# power.net
KiCad netlist of a schematic drawn in Altium Designer
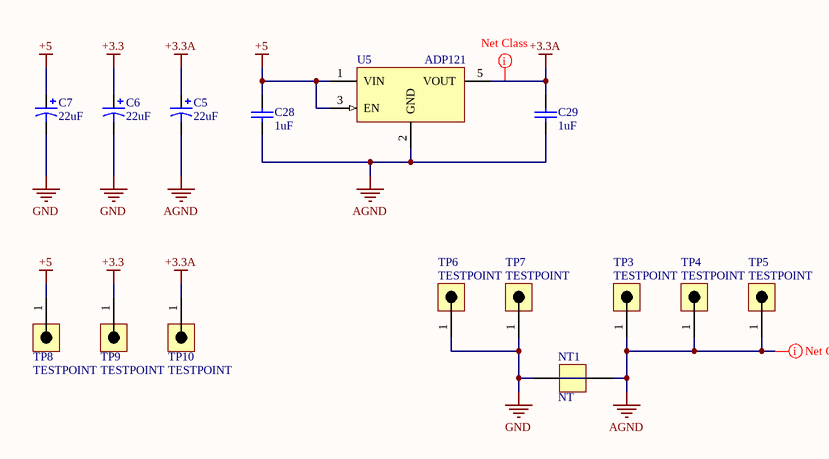
[diagram p0: power.SchDoc]

(export (version "E")
  (design (tool "Eeschema 10.0.6"))
  (components
    (comp (ref "C5")
      (value "22uF")
      (footprint "C0805")
      (description "Polarized Capacitor (Radial)")
      (fields (field (name "Comment") "Cap Pol1") (field (name "PUBLISHER") "Altium Limited"))
      (libsource (lib "Miscellaneous Devices") (part "Cap Pol1"))
    )
    (comp (ref "C6")
      (value "22uF")
      (footprint "C0805")
      (description "Polarized Capacitor (Radial)")
      (fields (field (name "Comment") "Cap Pol1") (field (name "PUBLISHER") "Altium Limited"))
      (libsource (lib "Miscellaneous Devices") (part "Cap Pol1"))
    )
    (comp (ref "C7")
      (value "22uF")
      (footprint "C0805")
      (description "Polarized Capacitor (Radial)")
      (fields (field (name "Comment") "Cap Pol1") (field (name "PUBLISHER") "Altium Limited"))
      (libsource (lib "Miscellaneous Devices") (part "Cap Pol1"))
    )
    (comp (ref "C28")
      (value "1uF")
      (footprint "C0603")
      (description "Capacitor")
      (fields (field (name "Comment") "Cap") (field (name "PUBLISHER") "Altium Limited"))
      (libsource (lib "Miscellaneous Devices") (part "Cap"))
    )
    (comp (ref "C29")
      (value "1uF")
      (footprint "C0603")
      (description "Capacitor")
      (fields (field (name "Comment") "Cap") (field (name "PUBLISHER") "Altium Limited"))
      (libsource (lib "Miscellaneous Devices") (part "Cap"))
    )
    (comp (ref "NT1")
      (value "NT")
      (footprint "NetTie")
      (description "NET TIE")
      (libsource (lib "net tie") (part "NT"))
    )
    (comp (ref "TP3")
      (value "TESTPOINT")
      (footprint "TESTPOINT")
      (description "TEST POINT")
      (libsource (lib "test point") (part "TESTPOINT"))
    )
    (comp (ref "TP4")
      (value "TESTPOINT")
      (footprint "TESTPOINT")
      (description "TEST POINT")
      (libsource (lib "test point") (part "TESTPOINT"))
    )
    (comp (ref "TP5")
      (value "TESTPOINT")
      (footprint "TESTPOINT")
      (description "TEST POINT")
      (libsource (lib "test point") (part "TESTPOINT"))
    )
    (comp (ref "TP6")
      (value "TESTPOINT")
      (footprint "TESTPOINT")
      (description "TEST POINT")
      (libsource (lib "test point") (part "TESTPOINT"))
    )
    (comp (ref "TP7")
      (value "TESTPOINT")
      (footprint "TESTPOINT")
      (description "TEST POINT")
      (libsource (lib "test point") (part "TESTPOINT"))
    )
    (comp (ref "TP8")
      (value "TESTPOINT")
      (footprint "TESTPOINT")
      (description "TEST POINT")
      (libsource (lib "") (part "TESTPOINT_1"))
    )
    (comp (ref "TP9")
      (value "TESTPOINT")
      (footprint "TESTPOINT")
      (description "TEST POINT")
      (libsource (lib "") (part "TESTPOINT_1"))
    )
    (comp (ref "TP10")
      (value "TESTPOINT")
      (footprint "TESTPOINT")
      (description "TEST POINT")
      (libsource (lib "") (part "TESTPOINT_1"))
    )
    (comp (ref "U5")
      (value "ADP121")
      (footprint "ADP121")
      (description "ANALOG DEVICES - ADP121-AUJZ33R7 - LDO, 150MA, 3.3V, TSOT-23-5")
      (libsource (lib "ADP121") (part "ADP121"))
    )
  )
  (nets
    (net (code "1") (name "+3.3") (class "Default")
      (node (ref "C6") (pin "1") (pinfunction "1_1") (pintype "passive"))
      (node (ref "TP9") (pin "1") (pinfunction "1_1") (pintype "passive"))
    )
    (net (code "2") (name "+3.3A") (class "Default")
      (node (ref "C29") (pin "2") (pinfunction "2_2") (pintype "passive"))
      (node (ref "C5") (pin "1") (pinfunction "1_1") (pintype "passive"))
      (node (ref "TP10") (pin "1") (pinfunction "1_1") (pintype "passive"))
      (node (ref "U5") (pin "5") (pinfunction "VOUT_5") (pintype "power_in"))
    )
    (net (code "3") (name "+5") (class "Default")
      (node (ref "C28") (pin "2") (pinfunction "2_2") (pintype "passive"))
      (node (ref "C7") (pin "1") (pinfunction "1_1") (pintype "passive"))
      (node (ref "TP8") (pin "1") (pinfunction "1_1") (pintype "passive"))
      (node (ref "U5") (pin "1") (pinfunction "VIN_1") (pintype "power_in"))
      (node (ref "U5") (pin "3") (pinfunction "EN_3") (pintype "input"))
    )
    (net (code "4") (name "AGND") (class "Default")
      (node (ref "C28") (pin "1") (pinfunction "1_1") (pintype "passive"))
      (node (ref "C29") (pin "1") (pinfunction "1_1") (pintype "passive"))
      (node (ref "C5") (pin "2") (pinfunction "2_2") (pintype "passive"))
      (node (ref "NT1") (pin "2") (pinfunction "2_2") (pintype "passive"))
      (node (ref "TP3") (pin "1") (pinfunction "1_1") (pintype "passive"))
      (node (ref "TP4") (pin "1") (pinfunction "1_1") (pintype "passive"))
      (node (ref "TP5") (pin "1") (pinfunction "1_1") (pintype "passive"))
      (node (ref "U5") (pin "2") (pinfunction "GND_2") (pintype "power_in"))
    )
    (net (code "5") (name "GND") (class "Default")
      (node (ref "C6") (pin "2") (pinfunction "2_2") (pintype "passive"))
      (node (ref "C7") (pin "2") (pinfunction "2_2") (pintype "passive"))
      (node (ref "NT1") (pin "1") (pinfunction "1_1") (pintype "passive"))
      (node (ref "TP6") (pin "1") (pinfunction "1_1") (pintype "passive"))
      (node (ref "TP7") (pin "1") (pinfunction "1_1") (pintype "passive"))
    )
  )
)
